# yalc.net
KiCad netlist of a schematic drawn in EAGLE
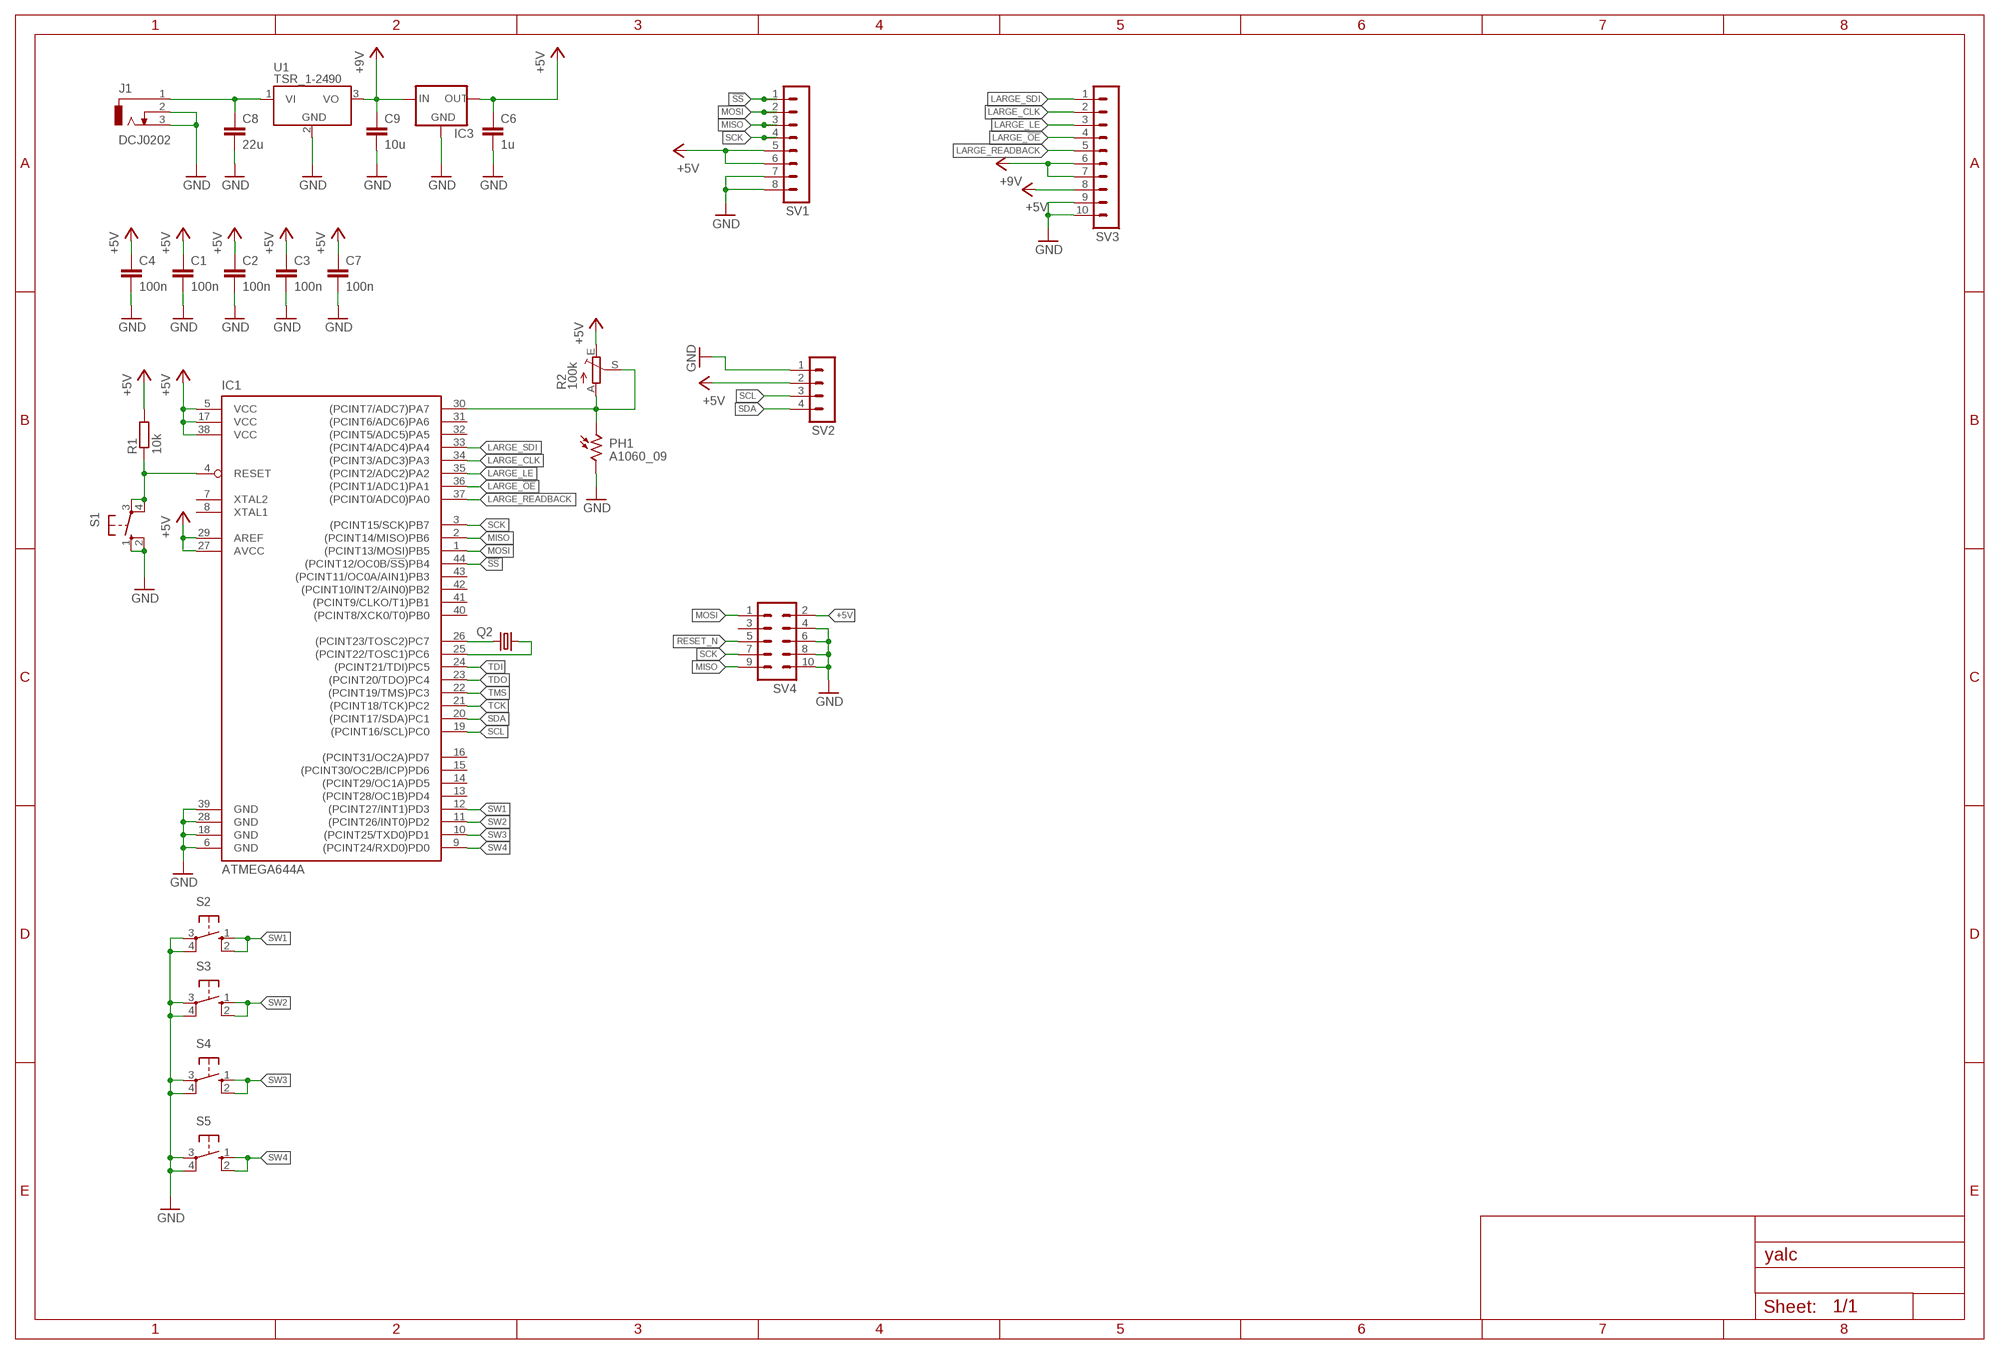
[diagram p0: schematic, sheet 1]

(export (version "E")
  (design (tool "Eeschema 10.0.6"))
  (components
    (comp (ref "C1")
      (value "100n")
      (footprint "eagle-import:C0805")
      (libsource (lib "eagle-import") (part "C-EUC0805"))
    )
    (comp (ref "C2")
      (value "100n")
      (footprint "eagle-import:C0805")
      (libsource (lib "eagle-import") (part "C-EUC0805"))
    )
    (comp (ref "C3")
      (value "100n")
      (footprint "eagle-import:C0805")
      (libsource (lib "eagle-import") (part "C-EUC0805"))
    )
    (comp (ref "C4")
      (value "100n")
      (footprint "eagle-import:C0805")
      (libsource (lib "eagle-import") (part "C-EUC0805"))
    )
    (comp (ref "C6")
      (value "1u")
      (footprint "eagle-import:C1206K")
      (libsource (lib "eagle-import") (part "C-EUC1206K"))
    )
    (comp (ref "C7")
      (value "100n")
      (footprint "eagle-import:C0805")
      (libsource (lib "eagle-import") (part "C-EUC0805"))
    )
    (comp (ref "C8")
      (value "22u")
      (footprint "eagle-import:C1206K")
      (libsource (lib "eagle-import") (part "C-EUC1206K"))
    )
    (comp (ref "C9")
      (value "10u")
      (footprint "eagle-import:C1206K")
      (libsource (lib "eagle-import") (part "C-EUC1206K"))
    )
    (comp (ref "IC1")
      (value "ATMEGA644A")
      (footprint "eagle-import:TQFP44")
      (fields (field (name "MPN") "ATMEGA644PV-10AU"))
      (libsource (lib "eagle-import") (part "ATMEGA644A"))
    )
    (comp (ref "IC3")
      (value "LFXXCVL")
      (footprint "eagle-import:TO220L1")
      (libsource (lib "eagle-import") (part "LFXXCVL"))
    )
    (comp (ref "J1")
      (value "DCJ0202")
      (footprint "eagle-import:DCJ0202")
      (libsource (lib "eagle-import") (part "DCJ0202"))
    )
    (comp (ref "PH1")
      (value "A1060_09")
      (footprint "eagle-import:T0-46-A10XX")
      (libsource (lib "eagle-import") (part "A1060_09"))
    )
    (comp (ref "Q2")
      (value "CRYSTALTC26H")
      (footprint "eagle-import:TC26H")
      (libsource (lib "eagle-import") (part "CRYSTALTC26H"))
    )
    (comp (ref "R1")
      (value "10k")
      (footprint "eagle-import:R0805")
      (libsource (lib "eagle-import") (part "R-EU_R0805"))
    )
    (comp (ref "R2")
      (value "100k")
      (footprint "eagle-import:ECP10S")
      (libsource (lib "eagle-import") (part "TRIM_EU-ECP10S"))
    )
    (comp (ref "S1")
      (value "10-XX")
      (footprint "eagle-import:B3F-10XX")
      (fields (field (name "MPN") "B3F-1000"))
      (libsource (lib "eagle-import") (part "10-XX"))
    )
    (comp (ref "S2")
      (value "10-XX")
      (footprint "eagle-import:B3F-10XX")
      (fields (field (name "MPN") "B3F-1000"))
      (libsource (lib "eagle-import") (part "10-XX"))
    )
    (comp (ref "S3")
      (value "10-XX")
      (footprint "eagle-import:B3F-10XX")
      (fields (field (name "MPN") "B3F-1000"))
      (libsource (lib "eagle-import") (part "10-XX"))
    )
    (comp (ref "S4")
      (value "10-XX")
      (footprint "eagle-import:B3F-10XX")
      (fields (field (name "MPN") "B3F-1000"))
      (libsource (lib "eagle-import") (part "10-XX"))
    )
    (comp (ref "S5")
      (value "10-XX")
      (footprint "eagle-import:B3F-10XX")
      (fields (field (name "MPN") "B3F-1000"))
      (libsource (lib "eagle-import") (part "10-XX"))
    )
    (comp (ref "SV1")
      (value "MA08-1W")
      (footprint "eagle-import:MA08-1W")
      (libsource (lib "eagle-import") (part "MA08-1W"))
    )
    (comp (ref "SV2")
      (value "MA04-1")
      (footprint "eagle-import:MA04-1")
      (libsource (lib "eagle-import") (part "MA04-1"))
    )
    (comp (ref "SV3")
      (value "MA10-1W")
      (footprint "eagle-import:MA10-1W")
      (fields (field (name "OC_FARNELL") "unknown") (field (name "OC_NEWARK") "unknown"))
      (libsource (lib "eagle-import") (part "MA10-1W"))
    )
    (comp (ref "SV4")
      (value "ML10")
      (footprint "eagle-import:ML10")
      (libsource (lib "eagle-import") (part "ML10"))
    )
    (comp (ref "U1")
      (value "TSR_1-2490")
      (footprint "eagle-import:TSR-1")
      (libsource (lib "eagle-import") (part "TSR_1-2490"))
    )
  )
  (nets
    (net (code "1") (name "+5V") (class "Default")
      (node (ref "C1") (pin "1") (pinfunction "1_1") (pintype "passive"))
      (node (ref "C2") (pin "1") (pinfunction "1_1") (pintype "passive"))
      (node (ref "C3") (pin "1") (pinfunction "1_1") (pintype "passive"))
      (node (ref "C4") (pin "1") (pinfunction "1_1") (pintype "passive"))
      (node (ref "C6") (pin "1") (pinfunction "1_1") (pintype "passive"))
      (node (ref "C7") (pin "1") (pinfunction "1_1") (pintype "passive"))
      (node (ref "IC1") (pin "17") (pinfunction "VCC_17") (pintype "power_in"))
      (node (ref "IC1") (pin "27") (pinfunction "AVCC_27") (pintype "power_in"))
      (node (ref "IC1") (pin "29") (pinfunction "AREF_29") (pintype "passive"))
      (node (ref "IC1") (pin "38") (pinfunction "VCC_38") (pintype "power_in"))
      (node (ref "IC1") (pin "5") (pinfunction "VCC_5") (pintype "power_in"))
      (node (ref "IC3") (pin "3") (pinfunction "OUT_3") (pintype "passive"))
      (node (ref "R1") (pin "2") (pinfunction "2_2") (pintype "passive"))
      (node (ref "R2") (pin "E") (pinfunction "E_E") (pintype "passive"))
      (node (ref "SV1") (pin "5") (pinfunction "5_5") (pintype "passive"))
      (node (ref "SV1") (pin "6") (pinfunction "6_6") (pintype "passive"))
      (node (ref "SV2") (pin "2") (pinfunction "2_2") (pintype "passive"))
      (node (ref "SV3") (pin "8") (pinfunction "8_8") (pintype "passive"))
      (node (ref "SV4") (pin "2") (pinfunction "2_2") (pintype "passive"))
    )
    (net (code "2") (name "+9V") (class "Default")
      (node (ref "C9") (pin "1") (pinfunction "1_1") (pintype "passive"))
      (node (ref "IC3") (pin "1") (pinfunction "IN_1") (pintype "input"))
      (node (ref "SV3") (pin "6") (pinfunction "6_6") (pintype "passive"))
      (node (ref "SV3") (pin "7") (pinfunction "7_7") (pintype "passive"))
      (node (ref "U1") (pin "3") (pinfunction "VO_3") (pintype "power_in"))
    )
    (net (code "3") (name "/LARGE_~{OE}") (class "Default")
      (node (ref "IC1") (pin "36") (pinfunction "(PCINT1/ADC1)PA1_36") (pintype "bidirectional"))
      (node (ref "SV3") (pin "4") (pinfunction "4_4") (pintype "passive"))
    )
    (net (code "4") (name "/~{SS}") (class "Default")
      (node (ref "IC1") (pin "44") (pinfunction "(PCINT12/OC0B/~{SS})PB4_44") (pintype "bidirectional"))
      (node (ref "SV1") (pin "1") (pinfunction "1_1") (pintype "passive"))
    )
    (net (code "5") (name "GND") (class "Default")
      (node (ref "C1") (pin "2") (pinfunction "2_2") (pintype "passive"))
      (node (ref "C2") (pin "2") (pinfunction "2_2") (pintype "passive"))
      (node (ref "C3") (pin "2") (pinfunction "2_2") (pintype "passive"))
      (node (ref "C4") (pin "2") (pinfunction "2_2") (pintype "passive"))
      (node (ref "C6") (pin "2") (pinfunction "2_2") (pintype "passive"))
      (node (ref "C7") (pin "2") (pinfunction "2_2") (pintype "passive"))
      (node (ref "C8") (pin "2") (pinfunction "2_2") (pintype "passive"))
      (node (ref "C9") (pin "2") (pinfunction "2_2") (pintype "passive"))
      (node (ref "IC1") (pin "18") (pinfunction "GND_18") (pintype "power_in"))
      (node (ref "IC1") (pin "28") (pinfunction "GND_28") (pintype "power_in"))
      (node (ref "IC1") (pin "39") (pinfunction "GND_39") (pintype "power_in"))
      (node (ref "IC1") (pin "6") (pinfunction "GND_6") (pintype "power_in"))
      (node (ref "IC3") (pin "2") (pinfunction "GND_2") (pintype "input"))
      (node (ref "J1") (pin "2") (pinfunction "2_2") (pintype "passive"))
      (node (ref "J1") (pin "3") (pinfunction "3_3") (pintype "passive"))
      (node (ref "PH1") (pin "2") (pinfunction "2_2") (pintype "passive"))
      (node (ref "S1") (pin "1") (pinfunction "S_1") (pintype "passive"))
      (node (ref "S1") (pin "2") (pinfunction "S1_2") (pintype "passive"))
      (node (ref "S2") (pin "3") (pinfunction "P_3") (pintype "passive"))
      (node (ref "S2") (pin "4") (pinfunction "P1_4") (pintype "passive"))
      (node (ref "S3") (pin "3") (pinfunction "P_3") (pintype "passive"))
      (node (ref "S3") (pin "4") (pinfunction "P1_4") (pintype "passive"))
      (node (ref "S4") (pin "3") (pinfunction "P_3") (pintype "passive"))
      (node (ref "S4") (pin "4") (pinfunction "P1_4") (pintype "passive"))
      (node (ref "S5") (pin "3") (pinfunction "P_3") (pintype "passive"))
      (node (ref "S5") (pin "4") (pinfunction "P1_4") (pintype "passive"))
      (node (ref "SV1") (pin "7") (pinfunction "7_7") (pintype "passive"))
      (node (ref "SV1") (pin "8") (pinfunction "8_8") (pintype "passive"))
      (node (ref "SV2") (pin "1") (pinfunction "1_1") (pintype "passive"))
      (node (ref "SV3") (pin "10") (pinfunction "10_10") (pintype "passive"))
      (node (ref "SV3") (pin "9") (pinfunction "9_9") (pintype "passive"))
      (node (ref "SV4") (pin "10") (pinfunction "10_10") (pintype "passive"))
      (node (ref "SV4") (pin "4") (pinfunction "4_4") (pintype "passive"))
      (node (ref "SV4") (pin "6") (pinfunction "6_6") (pintype "passive"))
      (node (ref "SV4") (pin "8") (pinfunction "8_8") (pintype "passive"))
      (node (ref "U1") (pin "2") (pinfunction "GND_2") (pintype "power_in"))
    )
    (net (code "6") (name "LARGE_CLK") (class "Default")
      (node (ref "IC1") (pin "34") (pinfunction "(PCINT3/ADC3)PA3_34") (pintype "bidirectional"))
      (node (ref "SV3") (pin "2") (pinfunction "2_2") (pintype "passive"))
    )
    (net (code "7") (name "LARGE_LE") (class "Default")
      (node (ref "IC1") (pin "35") (pinfunction "(PCINT2/ADC2)PA2_35") (pintype "bidirectional"))
      (node (ref "SV3") (pin "3") (pinfunction "3_3") (pintype "passive"))
    )
    (net (code "8") (name "LARGE_READBACK") (class "Default")
      (node (ref "IC1") (pin "37") (pinfunction "(PCINT0/ADC0)PA0_37") (pintype "bidirectional"))
      (node (ref "SV3") (pin "5") (pinfunction "5_5") (pintype "passive"))
    )
    (net (code "9") (name "LARGE_SDI") (class "Default")
      (node (ref "IC1") (pin "33") (pinfunction "(PCINT4/ADC4)PA4_33") (pintype "bidirectional"))
      (node (ref "SV3") (pin "1") (pinfunction "1_1") (pintype "passive"))
    )
    (net (code "10") (name "MISO") (class "Default")
      (node (ref "IC1") (pin "2") (pinfunction "(PCINT14/MISO)PB6_2") (pintype "bidirectional"))
      (node (ref "SV1") (pin "3") (pinfunction "3_3") (pintype "passive"))
      (node (ref "SV4") (pin "9") (pinfunction "9_9") (pintype "passive"))
    )
    (net (code "11") (name "MOSI") (class "Default")
      (node (ref "IC1") (pin "1") (pinfunction "(PCINT13/MOSI)PB5_1") (pintype "bidirectional"))
      (node (ref "SV1") (pin "2") (pinfunction "2_2") (pintype "passive"))
      (node (ref "SV4") (pin "1") (pinfunction "1_1") (pintype "passive"))
    )
    (net (code "12") (name "Net-(IC1-(PCINT7{slash}ADC7)PA7)") (class "Default")
      (node (ref "IC1") (pin "30") (pinfunction "(PCINT7/ADC7)PA7_30") (pintype "bidirectional"))
      (node (ref "PH1") (pin "1") (pinfunction "1_1") (pintype "passive"))
      (node (ref "R2") (pin "A") (pinfunction "A_A") (pintype "passive"))
      (node (ref "R2") (pin "S") (pinfunction "S_S") (pintype "passive"))
    )
    (net (code "13") (name "Net-(IC1-(PCINT22{slash}TOSC1)PC6)") (class "Default")
      (node (ref "IC1") (pin "25") (pinfunction "(PCINT22/TOSC1)PC6_25") (pintype "output"))
      (node (ref "Q2") (pin "1") (pinfunction "1_1") (pintype "passive"))
    )
    (net (code "14") (name "Net-(IC1-(PCINT23{slash}TOSC2)PC7)") (class "Default")
      (node (ref "IC1") (pin "26") (pinfunction "(PCINT23/TOSC2)PC7_26") (pintype "output"))
      (node (ref "Q2") (pin "2") (pinfunction "2_2") (pintype "passive"))
    )
    (net (code "15") (name "Net-(U1-VI)") (class "Default")
      (node (ref "C8") (pin "1") (pinfunction "1_1") (pintype "passive"))
      (node (ref "J1") (pin "1") (pinfunction "1_1") (pintype "passive"))
      (node (ref "U1") (pin "1") (pinfunction "VI_1") (pintype "power_in"))
    )
    (net (code "16") (name "RESET_N") (class "Default")
      (node (ref "IC1") (pin "4") (pinfunction "RESET_4") (pintype "input"))
      (node (ref "R1") (pin "1") (pinfunction "1_1") (pintype "passive"))
      (node (ref "S1") (pin "3") (pinfunction "P_3") (pintype "passive"))
      (node (ref "S1") (pin "4") (pinfunction "P1_4") (pintype "passive"))
      (node (ref "SV4") (pin "5") (pinfunction "5_5") (pintype "passive"))
    )
    (net (code "17") (name "SCK") (class "Default")
      (node (ref "IC1") (pin "3") (pinfunction "(PCINT15/SCK)PB7_3") (pintype "bidirectional"))
      (node (ref "SV1") (pin "4") (pinfunction "4_4") (pintype "passive"))
      (node (ref "SV4") (pin "7") (pinfunction "7_7") (pintype "passive"))
    )
    (net (code "18") (name "SCL") (class "Default")
      (node (ref "IC1") (pin "19") (pinfunction "(PCINT16/SCL)PC0_19") (pintype "output"))
      (node (ref "SV2") (pin "3") (pinfunction "3_3") (pintype "passive"))
    )
    (net (code "19") (name "SDA") (class "Default")
      (node (ref "IC1") (pin "20") (pinfunction "(PCINT17/SDA)PC1_20") (pintype "output"))
      (node (ref "SV2") (pin "4") (pinfunction "4_4") (pintype "passive"))
    )
    (net (code "20") (name "SW1") (class "Default")
      (node (ref "IC1") (pin "12") (pinfunction "(PCINT27/INT1)PD3_12") (pintype "bidirectional"))
      (node (ref "S2") (pin "1") (pinfunction "S_1") (pintype "passive"))
      (node (ref "S2") (pin "2") (pinfunction "S1_2") (pintype "passive"))
    )
    (net (code "21") (name "SW2") (class "Default")
      (node (ref "IC1") (pin "11") (pinfunction "(PCINT26/INT0)PD2_11") (pintype "bidirectional"))
      (node (ref "S3") (pin "1") (pinfunction "S_1") (pintype "passive"))
      (node (ref "S3") (pin "2") (pinfunction "S1_2") (pintype "passive"))
    )
    (net (code "22") (name "SW3") (class "Default")
      (node (ref "IC1") (pin "10") (pinfunction "(PCINT25/TXD0)PD1_10") (pintype "bidirectional"))
      (node (ref "S4") (pin "1") (pinfunction "S_1") (pintype "passive"))
      (node (ref "S4") (pin "2") (pinfunction "S1_2") (pintype "passive"))
    )
    (net (code "23") (name "SW4") (class "Default")
      (node (ref "IC1") (pin "9") (pinfunction "(PCINT24/RXD0)PD0_9") (pintype "bidirectional"))
      (node (ref "S5") (pin "1") (pinfunction "S_1") (pintype "passive"))
      (node (ref "S5") (pin "2") (pinfunction "S1_2") (pintype "passive"))
    )
    (net (code "24") (name "TCK") (class "Default")
      (node (ref "IC1") (pin "21") (pinfunction "(PCINT18/TCK)PC2_21") (pintype "output"))
    )
    (net (code "25") (name "TDI") (class "Default")
      (node (ref "IC1") (pin "24") (pinfunction "(PCINT21/TDI)PC5_24") (pintype "output"))
    )
    (net (code "26") (name "TDO") (class "Default")
      (node (ref "IC1") (pin "23") (pinfunction "(PCINT20/TDO)PC4_23") (pintype "output"))
    )
    (net (code "27") (name "TMS") (class "Default")
      (node (ref "IC1") (pin "22") (pinfunction "(PCINT19/TMS)PC3_22") (pintype "output"))
    )
    (net (code "28") (name "unconnected-(IC1-(PCINT5{slash}ADC5)PA5-Pad32)") (class "Default")
      (node (ref "IC1") (pin "32") (pinfunction "(PCINT5/ADC5)PA5_32") (pintype "bidirectional"))
    )
    (net (code "29") (name "unconnected-(IC1-(PCINT6{slash}ADC6)PA6-Pad31)") (class "Default")
      (node (ref "IC1") (pin "31") (pinfunction "(PCINT6/ADC6)PA6_31") (pintype "bidirectional"))
    )
    (net (code "30") (name "unconnected-(IC1-(PCINT8{slash}XCK0{slash}T0)PB0-Pad40)") (class "Default")
      (node (ref "IC1") (pin "40") (pinfunction "(PCINT8/XCK0/T0)PB0_40") (pintype "bidirectional"))
    )
    (net (code "31") (name "unconnected-(IC1-(PCINT9{slash}CLKO{slash}T1)PB1-Pad41)") (class "Default")
      (node (ref "IC1") (pin "41") (pinfunction "(PCINT9/CLKO/T1)PB1_41") (pintype "bidirectional"))
    )
    (net (code "32") (name "unconnected-(IC1-(PCINT10{slash}INT2{slash}AIN0)PB2-Pad42)") (class "Default")
      (node (ref "IC1") (pin "42") (pinfunction "(PCINT10/INT2/AIN0)PB2_42") (pintype "bidirectional"))
    )
    (net (code "33") (name "unconnected-(IC1-(PCINT11{slash}OC0A{slash}AIN1)PB3-Pad43)") (class "Default")
      (node (ref "IC1") (pin "43") (pinfunction "(PCINT11/OC0A/AIN1)PB3_43") (pintype "bidirectional"))
    )
    (net (code "34") (name "unconnected-(IC1-(PCINT28{slash}OC1B)PD4-Pad13)") (class "Default")
      (node (ref "IC1") (pin "13") (pinfunction "(PCINT28/OC1B)PD4_13") (pintype "bidirectional"))
    )
    (net (code "35") (name "unconnected-(IC1-(PCINT29{slash}OC1A)PD5-Pad14)") (class "Default")
      (node (ref "IC1") (pin "14") (pinfunction "(PCINT29/OC1A)PD5_14") (pintype "bidirectional"))
    )
    (net (code "36") (name "unconnected-(IC1-(PCINT30{slash}OC2B{slash}ICP)PD6-Pad15)") (class "Default")
      (node (ref "IC1") (pin "15") (pinfunction "(PCINT30/OC2B/ICP)PD6_15") (pintype "bidirectional"))
    )
    (net (code "37") (name "unconnected-(IC1-(PCINT31{slash}OC2A)PD7-Pad16)") (class "Default")
      (node (ref "IC1") (pin "16") (pinfunction "(PCINT31/OC2A)PD7_16") (pintype "bidirectional"))
    )
    (net (code "38") (name "unconnected-(IC1-XTAL1-Pad8)") (class "Default")
      (node (ref "IC1") (pin "8") (pinfunction "XTAL1_8") (pintype "bidirectional"))
    )
    (net (code "39") (name "unconnected-(IC1-XTAL2-Pad7)") (class "Default")
      (node (ref "IC1") (pin "7") (pinfunction "XTAL2_7") (pintype "bidirectional"))
    )
    (net (code "40") (name "unconnected-(SV4-Pad3)") (class "Default")
      (node (ref "SV4") (pin "3") (pinfunction "3_3") (pintype "passive"))
    )
  )
)
